# usb_conn_breakout.net
KiCad netlist of a schematic drawn in EasyEDA Pro
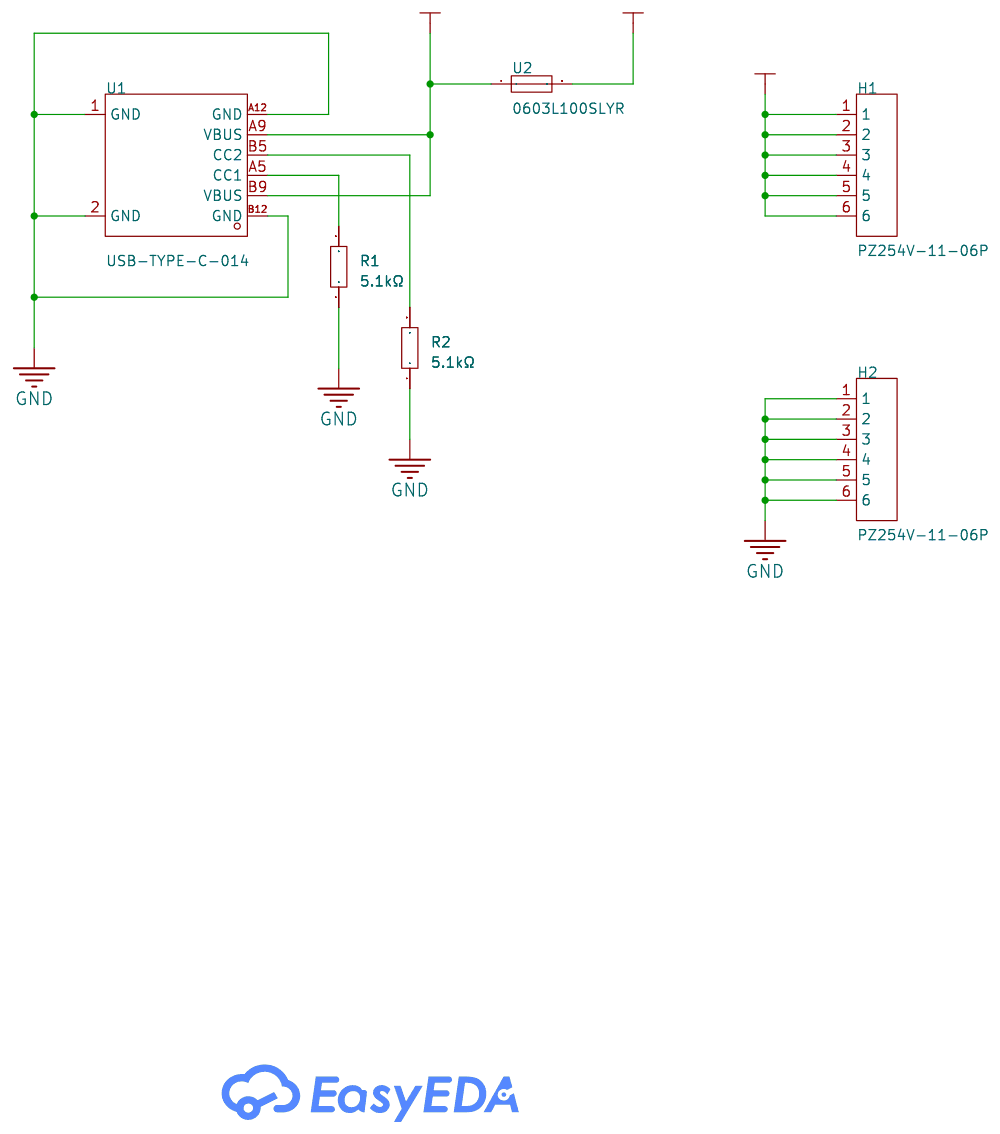
[diagram p0: schematic sheet]

(export (version "E")
  (design (tool "Eeschema 10.0.6"))
  (components
    (comp (ref "H1")
      (value "PZ254V-11-06P")
      (footprint "easyedapro:HDR-TH_6P-P2.54-V-M")
      (fields (field (name "Manufacturer") "XFCN(兴飞)"))
      (libsource (lib "easyedapro") (part "PZ254V-11-06P"))
    )
    (comp (ref "H2")
      (value "PZ254V-11-06P")
      (footprint "easyedapro:HDR-TH_6P-P2.54-V-M")
      (fields (field (name "Manufacturer") "XFCN(兴飞)"))
      (libsource (lib "easyedapro") (part "PZ254V-11-06P"))
    )
    (comp (ref "R1")
      (value "5.1kΩ")
      (footprint "easyedapro:R0805")
      (fields
        (field (name "Manufacturer Part") "0805W8F1002T5E")
        (field (name "Manufacturer") "UNI-ROYAL(厚声)")
      )
      (libsource (lib "easyedapro") (part "0805W8F1002T5E"))
    )
    (comp (ref "R2")
      (value "5.1kΩ")
      (footprint "easyedapro:R0805")
      (fields
        (field (name "Manufacturer Part") "0805W8F1002T5E")
        (field (name "Manufacturer") "UNI-ROYAL(厚声)")
      )
      (libsource (lib "easyedapro") (part "0805W8F1002T5E"))
    )
    (comp (ref "U1")
      (value "USB-TYPE-C-014")
      (footprint "easyedapro:USB-C-TH_USB-TYPE-C-014")
      (fields (field (name "Manufacturer") "DEALON(德艺隆)"))
      (libsource (lib "easyedapro") (part "USB-TYPE-C-014"))
    )
    (comp (ref "U2")
      (value "0603L100SLYR")
      (footprint "easyedapro:R0603")
      (fields (field (name "Manufacturer") "Littelfuse(美国力特)"))
      (libsource (lib "easyedapro") (part "0603L100SLYR"))
    )
  )
  (nets
    (net (code "1") (name "+5V_USB") (class "Default")
      (node (ref "H1") (pin "1") (pinfunction "1_1") (pintype "unspecified"))
      (node (ref "H1") (pin "2") (pinfunction "2_2") (pintype "unspecified"))
      (node (ref "H1") (pin "3") (pinfunction "3_3") (pintype "unspecified"))
      (node (ref "H1") (pin "4") (pinfunction "4_4") (pintype "unspecified"))
      (node (ref "H1") (pin "5") (pinfunction "5_5") (pintype "unspecified"))
      (node (ref "H1") (pin "6") (pinfunction "6_6") (pintype "unspecified"))
      (node (ref "U2") (pin "2") (pinfunction "2_2") (pintype "input"))
    )
    (net (code "2") (name "+5V_USB_UF") (class "Default")
      (node (ref "U1") (pin "A9") (pinfunction "VBUS_A9") (pintype "unspecified"))
      (node (ref "U1") (pin "B9") (pinfunction "VBUS_B9") (pintype "unspecified"))
      (node (ref "U2") (pin "1") (pinfunction "1_1") (pintype "input"))
    )
    (net (code "3") (name "GND") (class "Default")
      (node (ref "H2") (pin "1") (pinfunction "1_1") (pintype "unspecified"))
      (node (ref "H2") (pin "2") (pinfunction "2_2") (pintype "unspecified"))
      (node (ref "H2") (pin "3") (pinfunction "3_3") (pintype "unspecified"))
      (node (ref "H2") (pin "4") (pinfunction "4_4") (pintype "unspecified"))
      (node (ref "H2") (pin "5") (pinfunction "5_5") (pintype "unspecified"))
      (node (ref "H2") (pin "6") (pinfunction "6_6") (pintype "unspecified"))
      (node (ref "R1") (pin "1") (pinfunction "1_1") (pintype "input"))
      (node (ref "R2") (pin "1") (pinfunction "1_1") (pintype "input"))
      (node (ref "U1") (pin "1") (pinfunction "GND_1") (pintype "unspecified"))
      (node (ref "U1") (pin "2") (pinfunction "GND_2") (pintype "unspecified"))
      (node (ref "U1") (pin "A12") (pinfunction "GND_A12") (pintype "unspecified"))
      (node (ref "U1") (pin "B12") (pinfunction "GND_B12") (pintype "unspecified"))
    )
    (net (code "4") (name "Net-(U1-CC1)") (class "Default")
      (node (ref "R1") (pin "2") (pinfunction "2_2") (pintype "input"))
      (node (ref "U1") (pin "A5") (pinfunction "CC1_A5") (pintype "unspecified"))
    )
    (net (code "5") (name "Net-(U1-CC2)") (class "Default")
      (node (ref "R2") (pin "2") (pinfunction "2_2") (pintype "input"))
      (node (ref "U1") (pin "B5") (pinfunction "CC2_B5") (pintype "unspecified"))
    )
  )
)
